# powersupply.net
KiCad netlist of a schematic drawn in Altium Designer
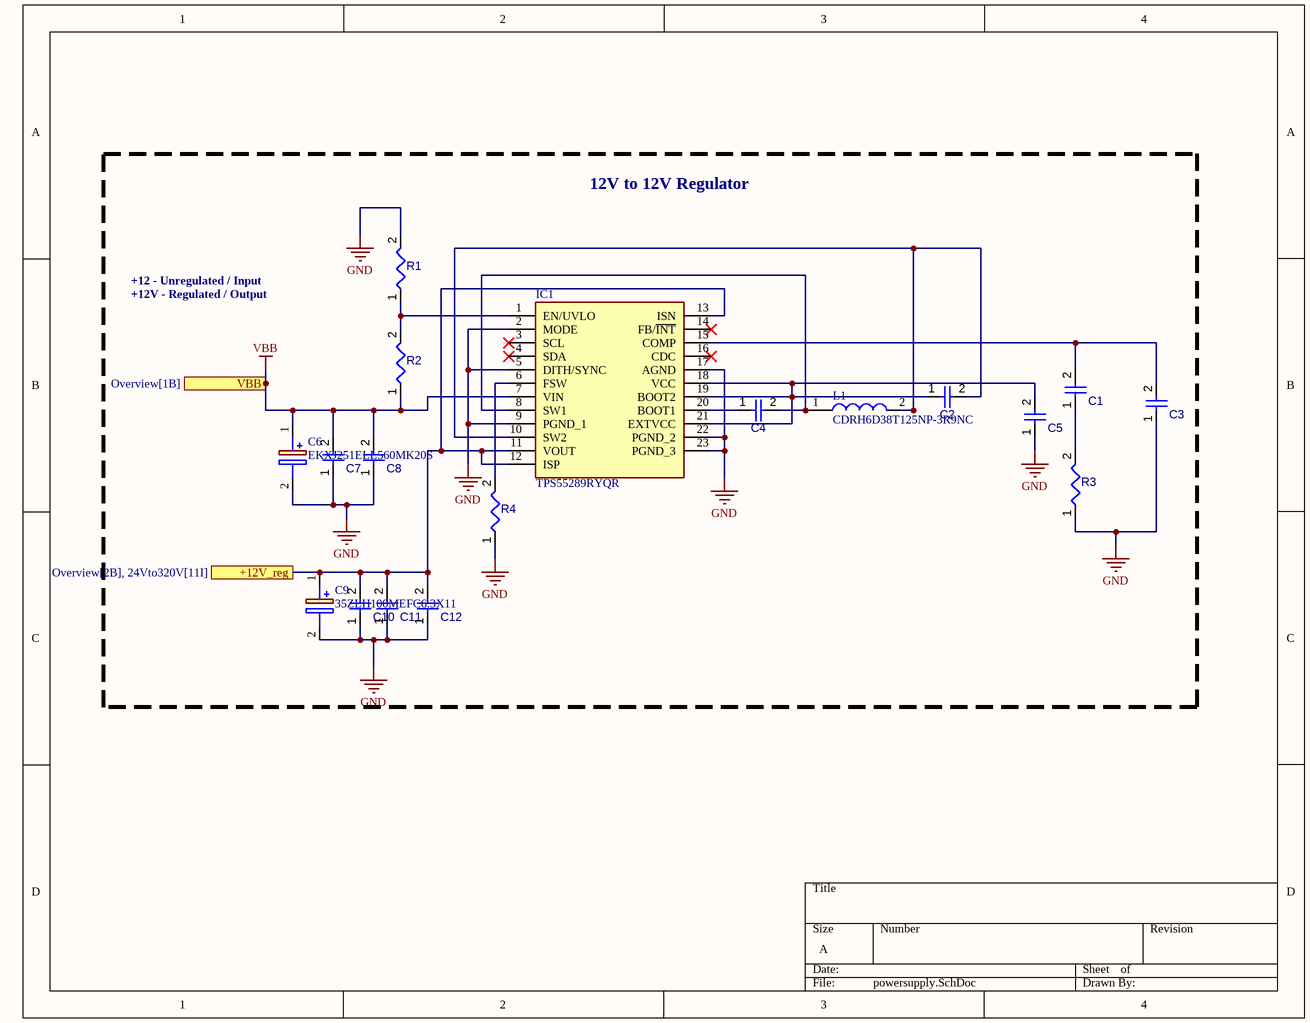
[diagram p0: powersupply.SchDoc]

(export (version "E")
  (design (tool "Eeschema 10.0.6"))
  (components
    (comp (ref "C1")
      (value "Capacitor 1nF +/-20% 50V 0402")
      (footprint "CAPC0402(1005)33_L")
      (description "Chip Capacitor, 1nF +/-20%, 50V, 0402, Thickness 0.33 mm")
      (fields (field (name "TOLERANCE") "10%"))
      (libsource (lib "Rahulb 23") (part "CAP-NP-2"))
    )
    (comp (ref "C2")
      (value "Capacitor 100 nF +/-10% 50 V 0603")
      (footprint "CAPC1608X90X40NL10T20")
      (description "Chip Capacitor, 100 nF, +/- 10%, 50 V, 0603 (1608 Metric)")
      (fields (field (name "TOLERANCE") "10%"))
      (libsource (lib "Rahulb 23") (part "CAP-NP-2"))
    )
    (comp (ref "C3")
      (value "Capacitor 1 uF +/- 10% 25 V 0805")
      (footprint "CAPC2013X145X50ML20T25")
      (description "Chip Capacitor, 5.1pF, +/-10%, 250 V, 0805 (2012 Metric)")
      (fields (field (name "TOLERANCE") "10%"))
      (libsource (lib "Rahulb 23") (part "CAP-NP-2"))
    )
    (comp (ref "C4")
      (value "Capacitor 100 nF +/-10% 50 V 0603")
      (footprint "CAPC1608X90X40NL10T20")
      (description "Chip Capacitor, 100 nF, +/- 10%, 50 V, 0603 (1608 Metric)")
      (fields (field (name "TOLERANCE") "10%"))
      (libsource (lib "Rahulb 23") (part "CAP-NP-2"))
    )
    (comp (ref "C5")
      (value "Capacitor 4.7µF +/-40% 25V 0805")
      (footprint "CAPC0805(2012)145_L")
      (description "Chip Capacitor, 4.7µF +/-40%, 25V, 0805, Thickness 1.45 mm")
      (fields (field (name "TOLERANCE") "20%"))
      (libsource (lib "Rahulb 23") (part "CAP-NP-2"))
    )
    (comp (ref "C6")
      (value "EKXJ251ELL560MK20S")
      (footprint "SamacSys:CAPPRD500W60D1275H2000")
      (description "56uF 250V Aluminum Electrolytic Capacitors Through Hole,D12.5xL20mm 10000hrs@105℃")
      (fields
        (field (name "MANUFACTURER_PART_NUMBER") "UPW0J222MHD")
        (field (name "MOUSER PART NUMBER") "647-UPW0J222MHD")
      )
      (libsource (lib "*") (part "UPW0J222MHD"))
    )
    (comp (ref "C7")
      (value "Capacitor 22µF +/-40% 16V 0805")
      (footprint "CAPC0805(2012)145_L")
      (description "Chip Capacitor, 22µF +/-20%, 25V, 0805, Thickness 1.45 mm X5R")
      (fields (field (name "TOLERANCE") "5%"))
      (libsource (lib "Rahulb 23") (part "CAP-NP-2"))
    )
    (comp (ref "C8")
      (value "Capacitor 1µF +/-40% 50V 0603")
      (footprint "CAPC0603(1608)100_L")
      (description "Chip Capacitor, 1µF +/-40%, 50V, 0603, Thickness 1 mm")
      (fields (field (name "TOLERANCE") "10%"))
      (libsource (lib "Rahulb 23") (part "CAP-NP-2"))
    )
    (comp (ref "C9")
      (value "35ZLH100MEFC6.3X11")
      (footprint "SamacSys:CAPPRD250W50D680H1250")
      (description "100uF 35V Aluminum Electrolytic Capacitors Through Hole,D6.3xL11mm 6000hrs@105℃")
      (fields
        (field (name "MANUFACTURER_PART_NUMBER") "MAL203856101E3")
        (field (name "MOUSER PART NUMBER") "594-MAL203856101E3")
      )
      (libsource (lib "*") (part "MAL203856101E3"))
    )
    (comp (ref "C10")
      (value "Capacitor 22µF +/-40% 16V 0805")
      (footprint "CAPC0805(2012)145_L")
      (description "Chip Capacitor, 22µF +/-20%, 25V, 0805, Thickness 1.45 mm X5R")
      (fields (field (name "TOLERANCE") "5%"))
      (libsource (lib "Rahulb 23") (part "CAP-NP-2"))
    )
    (comp (ref "C11")
      (value "Capacitor 22µF +/-40% 16V 0805")
      (footprint "CAPC0805(2012)145_L")
      (description "Chip Capacitor, 22µF +/-20%, 25V, 0805, Thickness 1.45 mm X5R")
      (fields (field (name "TOLERANCE") "5%"))
      (libsource (lib "Rahulb 23") (part "CAP-NP-2"))
    )
    (comp (ref "C12")
      (value "Capacitor 1µF +/-40% 50V 0603")
      (footprint "CAPC0603(1608)100_L")
      (description "Chip Capacitor, 1µF +/-40%, 50V, 0603, Thickness 1 mm")
      (fields (field (name "TOLERANCE") "10%"))
      (libsource (lib "Rahulb 23") (part "CAP-NP-2"))
    )
    (comp (ref "IC1")
      (value "TPS55289RYQR")
      (footprint "SamacSys:TPS55289RYQR")
      (description "Integrated Circuit")
      (fields (field (name "MOUSER PART NUMBER") "595-TPS55289RYQR"))
      (libsource (lib "SamacSys") (part "TPS55289RYQR"))
    )
    (comp (ref "L1")
      (value "CDRH6D38T125NP-3R9NC")
      (footprint "SamacSys:CDRH6D18HPNP101PC")
      (description "Inductor 3.9uH ,19.6mOhm, SMD, 6.7mm X 6.7mm")
      (fields (field (name "MANUFACTURER_PART_NUMBER") "CDRH6D18HPNP-101PC"))
      (libsource (lib "*") (part "CDRH6D18HPNP-101PC"))
    )
    (comp (ref "R1")
      (value "Resistor 100k +/-1% 1206 250 mW")
      (footprint "RESC3216X60X45ML15T20")
      (description "Chip Resistor, 100 KOhm, +/- 1%, 0.25 W, -55 to 155 degC, 1206 (3216 Metric)")
      (fields (field (name "TOLERANCE") "1%") (field (name "POWER") "250mW"))
      (libsource (lib "Rahulb 23") (part "RES-2"))
    )
    (comp (ref "R2")
      (value "Resistor 100k +/-1% 0603 100 mW")
      (footprint "RESC1608X55X25ML10T15")
      (description "Chip Resistor, 715 KOhm, +/- 1%, 0.1 W, -55 to 155 degC, 0603 (1608 Metric)")
      (fields (field (name "TOLERANCE") "1%") (field (name "POWER") "100mW"))
      (libsource (lib "Rahulb 23") (part "RES-2"))
    )
    (comp (ref "R3")
      (value "Resistor 100k +/-1% 0603 100 mW")
      (footprint "RESC1608X55X25ML10T15")
      (description "Chip Resistor, 105 KOhm, +/- 1%, 0.1 W, -55 to 155 degC, 0603 (1608 Metric)")
      (fields (field (name "TOLERANCE") "1%") (field (name "POWER") "100mW"))
      (libsource (lib "Rahulb 23") (part "RES-2"))
    )
    (comp (ref "R4")
      (value "Resistor 100k +/-1% 1206 250 mW")
      (footprint "RESC3216X60X45ML15T20")
      (description "Chip Resistor, 48.7 KOhm, +/- 1%, 0.25 W, -55 to 155 degC, 200V, 1206 (3216 Metric)")
      (fields (field (name "TOLERANCE") "1%") (field (name "POWER") "250mW"))
      (libsource (lib "Rahulb 23") (part "RES-2"))
    )
  )
  (nets
    (net (code "1") (name "/+12V_reg") (class "Default")
      (node (ref "C10") (pin "2") (pinfunction "2_2") (pintype "passive"))
      (node (ref "C11") (pin "2") (pinfunction "2_2") (pintype "passive"))
      (node (ref "C12") (pin "2") (pinfunction "2_2") (pintype "passive"))
      (node (ref "C9") (pin "1") (pinfunction "+_1") (pintype "passive"))
      (node (ref "IC1") (pin "11") (pinfunction "VOUT_11") (pintype "passive"))
      (node (ref "IC1") (pin "12") (pinfunction "ISP_12") (pintype "passive"))
      (node (ref "IC1") (pin "13") (pinfunction "ISN_13") (pintype "passive"))
    )
    (net (code "2") (name "GND") (class "Default")
      (node (ref "C10") (pin "1") (pinfunction "1_1") (pintype "passive"))
      (node (ref "C11") (pin "1") (pinfunction "1_1") (pintype "passive"))
      (node (ref "C12") (pin "1") (pinfunction "1_1") (pintype "passive"))
      (node (ref "C3") (pin "1") (pinfunction "1_1") (pintype "passive"))
      (node (ref "C5") (pin "1") (pinfunction "1_1") (pintype "passive"))
      (node (ref "C6") (pin "2") (pinfunction "-_2") (pintype "passive"))
      (node (ref "C7") (pin "1") (pinfunction "1_1") (pintype "passive"))
      (node (ref "C8") (pin "1") (pinfunction "1_1") (pintype "passive"))
      (node (ref "C9") (pin "2") (pinfunction "-_2") (pintype "passive"))
      (node (ref "IC1") (pin "17") (pinfunction "AGND_17") (pintype "passive"))
      (node (ref "IC1") (pin "2") (pinfunction "MODE_2") (pintype "passive"))
      (node (ref "IC1") (pin "22") (pinfunction "PGND_2_22") (pintype "passive"))
      (node (ref "IC1") (pin "23") (pinfunction "PGND_3_23") (pintype "passive"))
      (node (ref "IC1") (pin "5") (pinfunction "DITH/SYNC_5") (pintype "passive"))
      (node (ref "IC1") (pin "9") (pinfunction "PGND_1_9") (pintype "passive"))
      (node (ref "R1") (pin "2") (pinfunction "2_2") (pintype "passive"))
      (node (ref "R3") (pin "1") (pinfunction "1_1") (pintype "passive"))
      (node (ref "R4") (pin "1") (pinfunction "1_1") (pintype "passive"))
    )
    (net (code "3") (name "Net-(C1-Pad1)") (class "Default")
      (node (ref "C1") (pin "1") (pinfunction "1_1") (pintype "passive"))
      (node (ref "R3") (pin "2") (pinfunction "2_2") (pintype "passive"))
    )
    (net (code "4") (name "Net-(IC1-BOOT1)") (class "Default")
      (node (ref "C4") (pin "1") (pinfunction "1_1") (pintype "passive"))
      (node (ref "IC1") (pin "20") (pinfunction "BOOT1_20") (pintype "passive"))
    )
    (net (code "5") (name "Net-(IC1-BOOT2)") (class "Default")
      (node (ref "C2") (pin "1") (pinfunction "1_1") (pintype "passive"))
      (node (ref "C5") (pin "2") (pinfunction "2_2") (pintype "passive"))
      (node (ref "IC1") (pin "18") (pinfunction "VCC_18") (pintype "passive"))
      (node (ref "IC1") (pin "19") (pinfunction "BOOT2_19") (pintype "passive"))
      (node (ref "IC1") (pin "21") (pinfunction "EXTVCC_21") (pintype "passive"))
    )
    (net (code "6") (name "Net-(IC1-COMP)") (class "Default")
      (node (ref "C1") (pin "2") (pinfunction "2_2") (pintype "passive"))
      (node (ref "C3") (pin "2") (pinfunction "2_2") (pintype "passive"))
      (node (ref "IC1") (pin "15") (pinfunction "COMP_15") (pintype "passive"))
    )
    (net (code "7") (name "Net-(IC1-EN{slash}UVLO)") (class "Default")
      (node (ref "IC1") (pin "1") (pinfunction "EN/UVLO_1") (pintype "passive"))
      (node (ref "R1") (pin "1") (pinfunction "1_1") (pintype "passive"))
      (node (ref "R2") (pin "2") (pinfunction "2_2") (pintype "passive"))
    )
    (net (code "8") (name "Net-(IC1-FSW)") (class "Default")
      (node (ref "IC1") (pin "6") (pinfunction "FSW_6") (pintype "passive"))
      (node (ref "R4") (pin "2") (pinfunction "2_2") (pintype "passive"))
    )
    (net (code "9") (name "Net-(IC1-SW1)") (class "Default")
      (node (ref "C4") (pin "2") (pinfunction "2_2") (pintype "passive"))
      (node (ref "IC1") (pin "8") (pinfunction "SW1_8") (pintype "passive"))
      (node (ref "L1") (pin "1") (pinfunction "1_1") (pintype "passive"))
    )
    (net (code "10") (name "Net-(IC1-SW2)") (class "Default")
      (node (ref "C2") (pin "2") (pinfunction "2_2") (pintype "passive"))
      (node (ref "IC1") (pin "10") (pinfunction "SW2_10") (pintype "passive"))
      (node (ref "L1") (pin "2") (pinfunction "2_2") (pintype "passive"))
    )
    (net (code "11") (name "VBB") (class "Default")
      (node (ref "C6") (pin "1") (pinfunction "+_1") (pintype "passive"))
      (node (ref "C7") (pin "2") (pinfunction "2_2") (pintype "passive"))
      (node (ref "C8") (pin "2") (pinfunction "2_2") (pintype "passive"))
      (node (ref "IC1") (pin "7") (pinfunction "VIN_7") (pintype "passive"))
      (node (ref "R2") (pin "1") (pinfunction "1_1") (pintype "passive"))
    )
    (net (code "12") (name "unconnected-(IC1-CDC-Pad16)") (class "Default")
      (node (ref "IC1") (pin "16") (pinfunction "CDC_16") (pintype "passive+no_connect"))
    )
    (net (code "13") (name "unconnected-(IC1-FB{slash}~{INT}-Pad14)") (class "Default")
      (node (ref "IC1") (pin "14") (pinfunction "FB/~{INT}_14") (pintype "passive+no_connect"))
    )
    (net (code "14") (name "unconnected-(IC1-SCL-Pad3)") (class "Default")
      (node (ref "IC1") (pin "3") (pinfunction "SCL_3") (pintype "passive+no_connect"))
    )
    (net (code "15") (name "unconnected-(IC1-SDA-Pad4)") (class "Default")
      (node (ref "IC1") (pin "4") (pinfunction "SDA_4") (pintype "passive+no_connect"))
    )
  )
)
